# Funkboard_v2.net
KiCad netlist of a schematic drawn in EAGLE
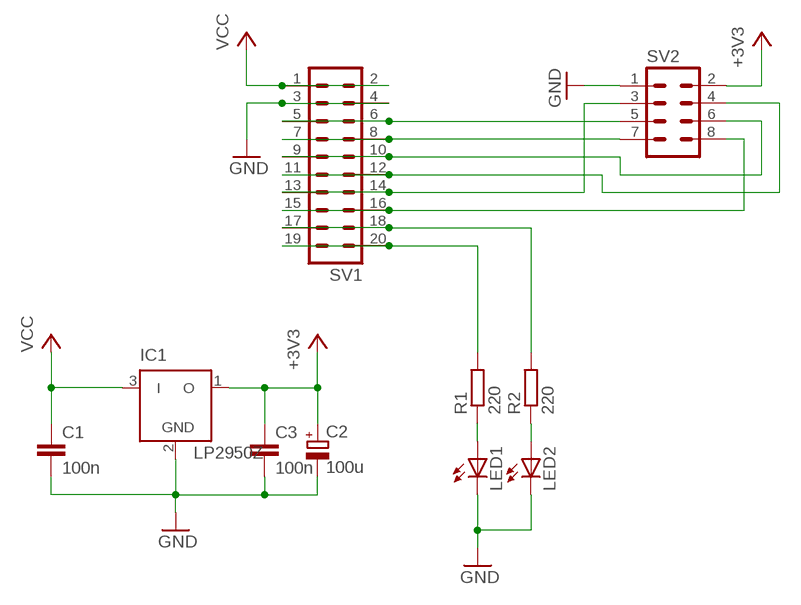
[diagram p0: schematic, sheet 1]

(export (version "E")
  (design (tool "Eeschema 10.0.6"))
  (components
    (comp (ref "C1")
      (value "100n")
      (footprint "eagle-import:C025-025X050")
      (libsource (lib "eagle-import") (part "C-EU025-025X050"))
    )
    (comp (ref "C2")
      (value "100u")
      (footprint "eagle-import:E2,5-6")
      (libsource (lib "eagle-import") (part "CPOL-EUE2.5-6"))
    )
    (comp (ref "C3")
      (value "100n")
      (footprint "eagle-import:C025-025X050")
      (libsource (lib "eagle-import") (part "C-EU025-025X050"))
    )
    (comp (ref "IC1")
      (value "LP2950Z")
      (footprint "eagle-import:TO92")
      (libsource (lib "eagle-import") (part "LP2950Z"))
    )
    (comp (ref "LED1")
      (value "LED3MM")
      (footprint "eagle-import:LED3MM")
      (libsource (lib "eagle-import") (part "LED3MM"))
    )
    (comp (ref "LED2")
      (value "LED3MM")
      (footprint "eagle-import:LED3MM")
      (libsource (lib "eagle-import") (part "LED3MM"))
    )
    (comp (ref "R1")
      (value "220")
      (footprint "eagle-import:0204V")
      (libsource (lib "eagle-import") (part "R-EU_0204/2V"))
    )
    (comp (ref "R2")
      (value "220")
      (footprint "eagle-import:0204V")
      (libsource (lib "eagle-import") (part "R-EU_0204/2V"))
    )
    (comp (ref "SV1")
      (value "MA10-2W")
      (footprint "eagle-import:MA10-2W")
      (libsource (lib "eagle-import") (part "MA10-2W"))
    )
    (comp (ref "SV2")
      (value "MA04-2")
      (footprint "eagle-import:MA04-2")
      (libsource (lib "eagle-import") (part "MA04-2"))
    )
  )
  (nets
    (net (code "1") (name "+3V3") (class "Default")
      (node (ref "C2") (pin "+") (pinfunction "+_+") (pintype "passive"))
      (node (ref "C3") (pin "1") (pinfunction "1_1") (pintype "passive"))
      (node (ref "IC1") (pin "1") (pinfunction "O_1") (pintype "input"))
      (node (ref "SV2") (pin "2") (pinfunction "2_2") (pintype "passive"))
    )
    (net (code "2") (name "GND") (class "Default")
      (node (ref "C1") (pin "2") (pinfunction "2_2") (pintype "passive"))
      (node (ref "C2") (pin "-") (pinfunction "-_-") (pintype "passive"))
      (node (ref "C3") (pin "2") (pinfunction "2_2") (pintype "passive"))
      (node (ref "IC1") (pin "2") (pinfunction "GND_2") (pintype "power_in"))
      (node (ref "LED1") (pin "K") (pinfunction "C_K") (pintype "passive"))
      (node (ref "LED2") (pin "K") (pinfunction "C_K") (pintype "passive"))
      (node (ref "SV1") (pin "3") (pinfunction "3_3") (pintype "passive"))
      (node (ref "SV1") (pin "4") (pinfunction "4_4") (pintype "passive"))
      (node (ref "SV2") (pin "1") (pinfunction "1_1") (pintype "passive"))
    )
    (net (code "3") (name "Net-(LED1-PadA)") (class "Default")
      (node (ref "LED1") (pin "A") (pinfunction "A_A") (pintype "passive"))
      (node (ref "R1") (pin "1") (pinfunction "1_1") (pintype "passive"))
    )
    (net (code "4") (name "Net-(LED2-PadA)") (class "Default")
      (node (ref "LED2") (pin "A") (pinfunction "A_A") (pintype "passive"))
      (node (ref "R2") (pin "1") (pinfunction "1_1") (pintype "passive"))
    )
    (net (code "5") (name "Net-(R1-Pad2)") (class "Default")
      (node (ref "R1") (pin "2") (pinfunction "2_2") (pintype "passive"))
      (node (ref "SV1") (pin "19") (pinfunction "19_19") (pintype "passive"))
      (node (ref "SV1") (pin "20") (pinfunction "20_20") (pintype "passive"))
    )
    (net (code "6") (name "Net-(R2-Pad2)") (class "Default")
      (node (ref "R2") (pin "2") (pinfunction "2_2") (pintype "passive"))
      (node (ref "SV1") (pin "17") (pinfunction "17_17") (pintype "passive"))
      (node (ref "SV1") (pin "18") (pinfunction "18_18") (pintype "passive"))
    )
    (net (code "7") (name "Net-(SV1-Pad5)") (class "Default")
      (node (ref "SV1") (pin "5") (pinfunction "5_5") (pintype "passive"))
      (node (ref "SV1") (pin "6") (pinfunction "6_6") (pintype "passive"))
      (node (ref "SV2") (pin "5") (pinfunction "5_5") (pintype "passive"))
    )
    (net (code "8") (name "Net-(SV1-Pad7)") (class "Default")
      (node (ref "SV1") (pin "7") (pinfunction "7_7") (pintype "passive"))
      (node (ref "SV1") (pin "8") (pinfunction "8_8") (pintype "passive"))
      (node (ref "SV2") (pin "7") (pinfunction "7_7") (pintype "passive"))
    )
    (net (code "9") (name "Net-(SV1-Pad10)") (class "Default")
      (node (ref "SV1") (pin "10") (pinfunction "10_10") (pintype "passive"))
      (node (ref "SV1") (pin "9") (pinfunction "9_9") (pintype "passive"))
      (node (ref "SV2") (pin "6") (pinfunction "6_6") (pintype "passive"))
    )
    (net (code "10") (name "Net-(SV1-Pad11)") (class "Default")
      (node (ref "SV1") (pin "11") (pinfunction "11_11") (pintype "passive"))
      (node (ref "SV1") (pin "12") (pinfunction "12_12") (pintype "passive"))
      (node (ref "SV2") (pin "4") (pinfunction "4_4") (pintype "passive"))
    )
    (net (code "11") (name "Net-(SV1-Pad13)") (class "Default")
      (node (ref "SV1") (pin "13") (pinfunction "13_13") (pintype "passive"))
      (node (ref "SV1") (pin "14") (pinfunction "14_14") (pintype "passive"))
      (node (ref "SV2") (pin "3") (pinfunction "3_3") (pintype "passive"))
    )
    (net (code "12") (name "Net-(SV1-Pad15)") (class "Default")
      (node (ref "SV1") (pin "15") (pinfunction "15_15") (pintype "passive"))
      (node (ref "SV1") (pin "16") (pinfunction "16_16") (pintype "passive"))
      (node (ref "SV2") (pin "8") (pinfunction "8_8") (pintype "passive"))
    )
    (net (code "13") (name "VCC") (class "Default")
      (node (ref "C1") (pin "1") (pinfunction "1_1") (pintype "passive"))
      (node (ref "IC1") (pin "3") (pinfunction "I_3") (pintype "input"))
      (node (ref "SV1") (pin "1") (pinfunction "1_1") (pintype "passive"))
      (node (ref "SV1") (pin "2") (pinfunction "2_2") (pintype "passive"))
    )
  )
)
